# ArduinoInterface_v4_1.net
KiCad netlist of a schematic drawn in EAGLE
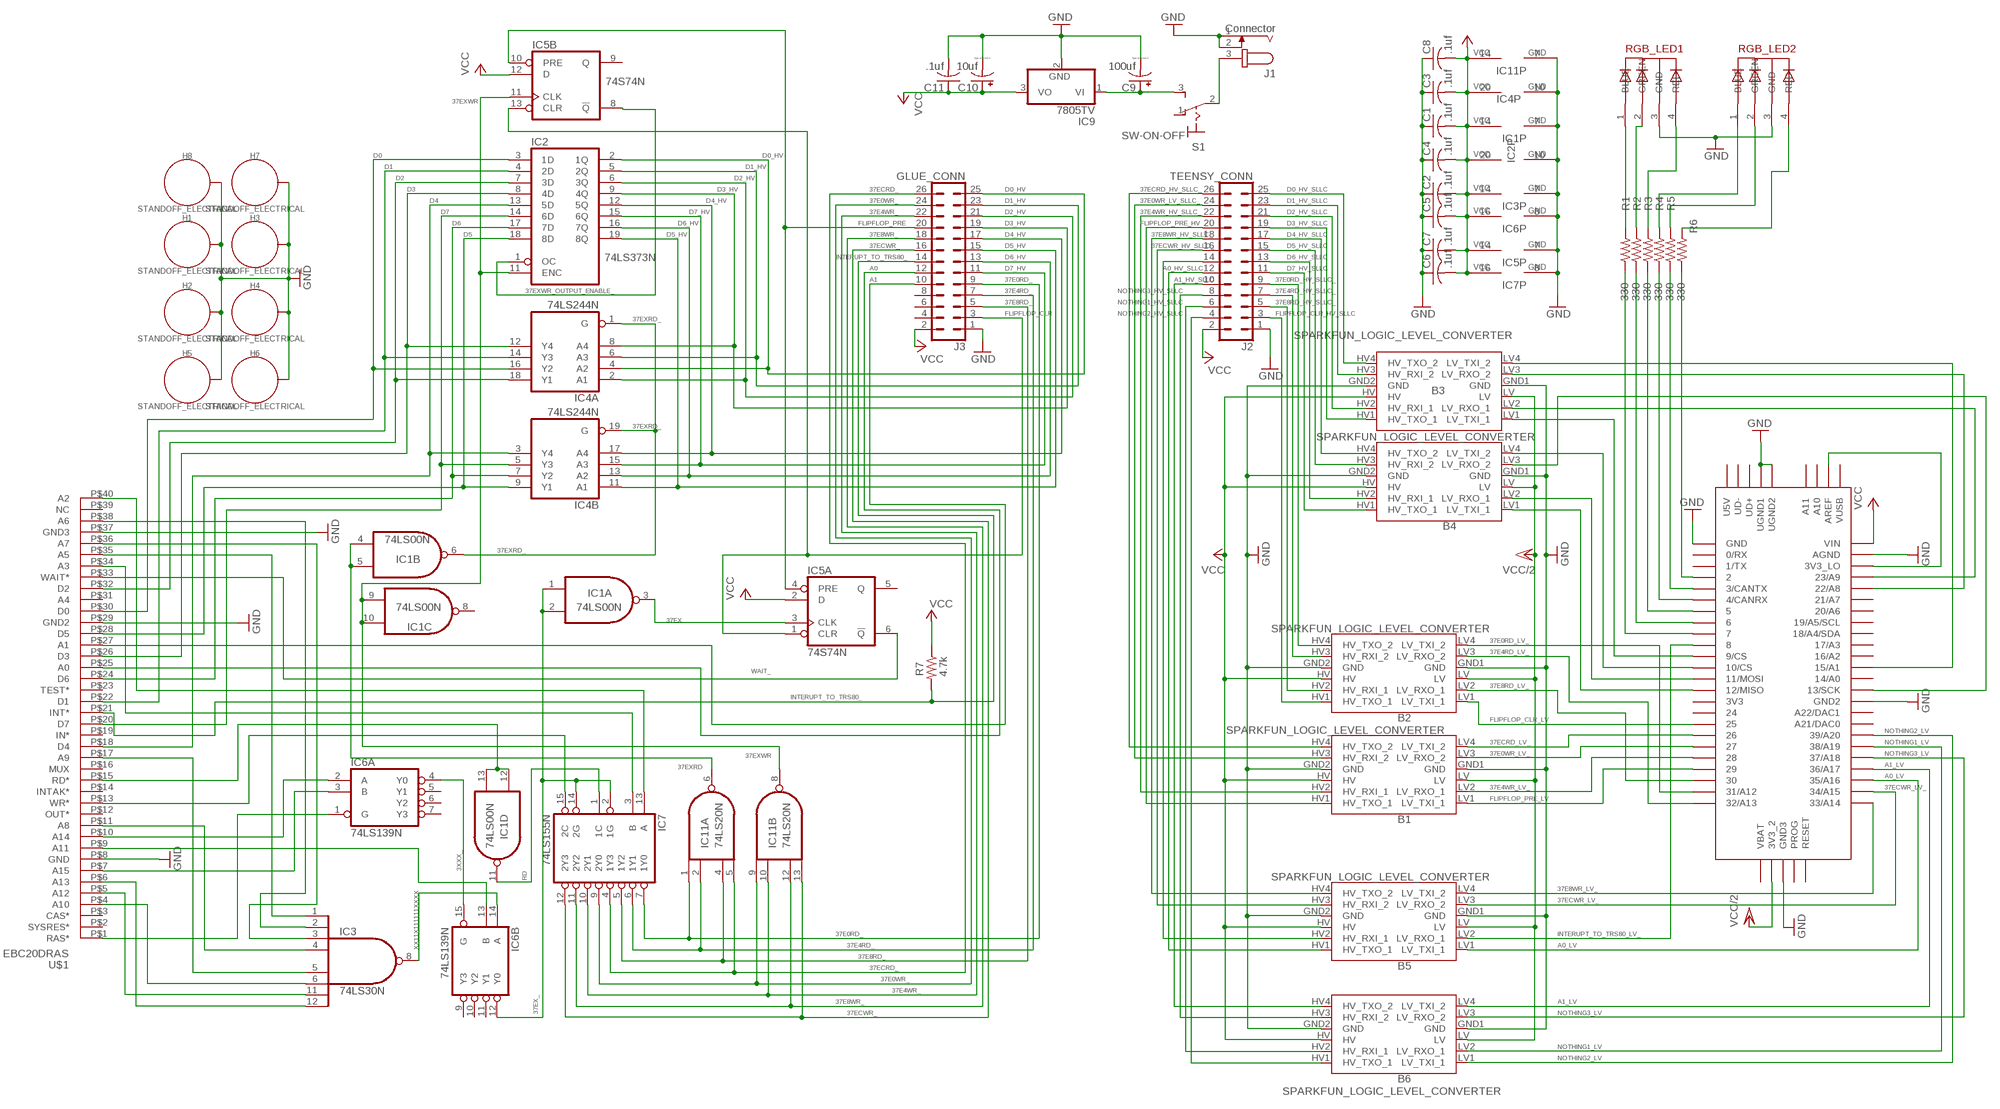
[diagram p0: schematic, sheet 1]

(export (version "E")
  (design (tool "Eeschema 10.0.6"))
  (components
    (comp (ref "B1")
      (value "SPARKFUN_LOGIC_LEVEL_CONVERTER")
      (footprint "eagle-import:SPARKFUN_LOGIC_LEVEL_CONVERTER")
      (libsource (lib "eagle-import") (part "SPARKFUN_LOGIC_LEVEL_CONVERTER"))
    )
    (comp (ref "B2")
      (value "SPARKFUN_LOGIC_LEVEL_CONVERTER")
      (footprint "eagle-import:SPARKFUN_LOGIC_LEVEL_CONVERTER")
      (libsource (lib "eagle-import") (part "SPARKFUN_LOGIC_LEVEL_CONVERTER"))
    )
    (comp (ref "B3")
      (value "SPARKFUN_LOGIC_LEVEL_CONVERTER")
      (footprint "eagle-import:SPARKFUN_LOGIC_LEVEL_CONVERTER")
      (libsource (lib "eagle-import") (part "SPARKFUN_LOGIC_LEVEL_CONVERTER"))
    )
    (comp (ref "B4")
      (value "SPARKFUN_LOGIC_LEVEL_CONVERTER")
      (footprint "eagle-import:SPARKFUN_LOGIC_LEVEL_CONVERTER")
      (libsource (lib "eagle-import") (part "SPARKFUN_LOGIC_LEVEL_CONVERTER"))
    )
    (comp (ref "B5")
      (value "SPARKFUN_LOGIC_LEVEL_CONVERTER")
      (footprint "eagle-import:SPARKFUN_LOGIC_LEVEL_CONVERTER")
      (libsource (lib "eagle-import") (part "SPARKFUN_LOGIC_LEVEL_CONVERTER"))
    )
    (comp (ref "B6")
      (value "SPARKFUN_LOGIC_LEVEL_CONVERTER")
      (footprint "eagle-import:SPARKFUN_LOGIC_LEVEL_CONVERTER")
      (libsource (lib "eagle-import") (part "SPARKFUN_LOGIC_LEVEL_CONVERTER"))
    )
    (comp (ref "C1")
      (value ".1uf")
      (footprint "eagle-import:C025-025X050")
      (libsource (lib "eagle-import") (part "C-US025-025X050"))
    )
    (comp (ref "C2")
      (value ".1uf")
      (footprint "eagle-import:C025-025X050")
      (libsource (lib "eagle-import") (part "C-US025-025X050"))
    )
    (comp (ref "C3")
      (value ".1uf")
      (footprint "eagle-import:C025-025X050")
      (libsource (lib "eagle-import") (part "C-US025-025X050"))
    )
    (comp (ref "C4")
      (value ".1uf")
      (footprint "eagle-import:C025-025X050")
      (libsource (lib "eagle-import") (part "C-US025-025X050"))
    )
    (comp (ref "C5")
      (value ".1uf")
      (footprint "eagle-import:C025-025X050")
      (libsource (lib "eagle-import") (part "C-US025-025X050"))
    )
    (comp (ref "C6")
      (value ".1uf")
      (footprint "eagle-import:C025-025X050")
      (libsource (lib "eagle-import") (part "C-US025-025X050"))
    )
    (comp (ref "C7")
      (value ".1uf")
      (footprint "eagle-import:C025-025X050")
      (libsource (lib "eagle-import") (part "C-US025-025X050"))
    )
    (comp (ref "C8")
      (value ".1uf")
      (footprint "eagle-import:C025-025X050")
      (libsource (lib "eagle-import") (part "C-US025-025X050"))
    )
    (comp (ref "C9")
      (value "100uf")
      (footprint "eagle-import:E5-6")
      (libsource (lib "eagle-import") (part "CPOL-USE5-6"))
    )
    (comp (ref "C10")
      (value "10uf")
      (footprint "eagle-import:E5-6")
      (libsource (lib "eagle-import") (part "CPOL-USE5-6"))
    )
    (comp (ref "C11")
      (value ".1uf")
      (footprint "eagle-import:C025-025X050")
      (libsource (lib "eagle-import") (part "C-US025-025X050"))
    )
    (comp (ref "H1")
      (value "STANDOFF_ELECTRICAL")
      (footprint "eagle-import:STANDOFF-ELECTRICAL")
      (libsource (lib "eagle-import") (part "STANDOFF_ELECTRICAL"))
    )
    (comp (ref "H2")
      (value "STANDOFF_ELECTRICAL")
      (footprint "eagle-import:STANDOFF-ELECTRICAL")
      (libsource (lib "eagle-import") (part "STANDOFF_ELECTRICAL"))
    )
    (comp (ref "H3")
      (value "STANDOFF_ELECTRICAL")
      (footprint "eagle-import:STANDOFF-ELECTRICAL")
      (libsource (lib "eagle-import") (part "STANDOFF_ELECTRICAL"))
    )
    (comp (ref "H4")
      (value "STANDOFF_ELECTRICAL")
      (footprint "eagle-import:STANDOFF-ELECTRICAL")
      (libsource (lib "eagle-import") (part "STANDOFF_ELECTRICAL"))
    )
    (comp (ref "H5")
      (value "STANDOFF_ELECTRICAL")
      (footprint "eagle-import:STANDOFF-ELECTRICAL")
      (libsource (lib "eagle-import") (part "STANDOFF_ELECTRICAL"))
    )
    (comp (ref "H6")
      (value "STANDOFF_ELECTRICAL")
      (footprint "eagle-import:STANDOFF-ELECTRICAL")
      (libsource (lib "eagle-import") (part "STANDOFF_ELECTRICAL"))
    )
    (comp (ref "H7")
      (value "STANDOFF_ELECTRICAL")
      (footprint "eagle-import:STANDOFF-ELECTRICAL")
      (libsource (lib "eagle-import") (part "STANDOFF_ELECTRICAL"))
    )
    (comp (ref "H8")
      (value "STANDOFF_ELECTRICAL")
      (footprint "eagle-import:STANDOFF-ELECTRICAL")
      (libsource (lib "eagle-import") (part "STANDOFF_ELECTRICAL"))
    )
    (comp (ref "IC1")
      (value "74LS00N")
      (footprint "eagle-import:DIL14")
      (libsource (lib "eagle-import") (part "7400NLS"))
    )
    (comp (ref "IC2")
      (value "74LS373N")
      (footprint "eagle-import:DIL20")
      (libsource (lib "eagle-import") (part "74373NLS"))
    )
    (comp (ref "IC3")
      (value "74LS30N")
      (footprint "eagle-import:DIL14")
      (libsource (lib "eagle-import") (part "7430NLS"))
    )
    (comp (ref "IC4")
      (value "74LS244N")
      (footprint "eagle-import:DIL20")
      (libsource (lib "eagle-import") (part "74244NLS"))
    )
    (comp (ref "IC5")
      (value "74S74N")
      (footprint "eagle-import:DIL14")
      (libsource (lib "eagle-import") (part "7474NS"))
    )
    (comp (ref "IC6")
      (value "74LS139N")
      (footprint "eagle-import:DIL16")
      (libsource (lib "eagle-import") (part "74139NLS"))
    )
    (comp (ref "IC7")
      (value "74LS155N")
      (footprint "eagle-import:DIL16")
      (libsource (lib "eagle-import") (part "74155NLS"))
    )
    (comp (ref "IC9")
      (value "7805TV")
      (footprint "eagle-import:TO220V")
      (libsource (lib "eagle-import") (part "78TV05"))
    )
    (comp (ref "IC11")
      (value "74LS20N")
      (footprint "eagle-import:DIL14")
      (libsource (lib "eagle-import") (part "7420NLS"))
    )
    (comp (ref "J1")
      (value "Connector")
      (footprint "eagle-import:SPC4077")
      (libsource (lib "eagle-import") (part "JACK-PLUG0"))
    )
    (comp (ref "J2")
      (value "TEENSY_CONN")
      (footprint "eagle-import:2X13")
      (libsource (lib "eagle-import") (part "CONN_13X22X13"))
    )
    (comp (ref "J3")
      (value "GLUE_CONN")
      (footprint "eagle-import:2X13")
      (libsource (lib "eagle-import") (part "CONN_13X22X13"))
    )
    (comp (ref "R1")
      (value "330")
      (footprint "eagle-import:0204V")
      (libsource (lib "eagle-import") (part "R-US_0204/2V"))
    )
    (comp (ref "R2")
      (value "330")
      (footprint "eagle-import:0204V")
      (libsource (lib "eagle-import") (part "R-US_0204/2V"))
    )
    (comp (ref "R3")
      (value "330")
      (footprint "eagle-import:0204V")
      (libsource (lib "eagle-import") (part "R-US_0204/2V"))
    )
    (comp (ref "R4")
      (value "330")
      (footprint "eagle-import:0204V")
      (libsource (lib "eagle-import") (part "R-US_0204/2V"))
    )
    (comp (ref "R5")
      (value "330")
      (footprint "eagle-import:0204V")
      (libsource (lib "eagle-import") (part "R-US_0204/2V"))
    )
    (comp (ref "R6")
      (value "330")
      (footprint "eagle-import:0204V")
      (libsource (lib "eagle-import") (part "R-US_0204/2V"))
    )
    (comp (ref "R7")
      (value "4.7k")
      (footprint "eagle-import:0204V")
      (libsource (lib "eagle-import") (part "R-US_0204/2V"))
    )
    (comp (ref "RGB_LED1")
      (value "5MMRGBLED")
      (footprint "eagle-import:LED5MMRGB")
      (libsource (lib "eagle-import") (part "5MMRGBLED"))
    )
    (comp (ref "RGB_LED2")
      (value "5MMRGBLED")
      (footprint "eagle-import:LED5MMRGB")
      (libsource (lib "eagle-import") (part "5MMRGBLED"))
    )
    (comp (ref "S1")
      (value "SW-ON-OFF")
      (footprint "eagle-import:M9040P")
      (libsource (lib "eagle-import") (part "M9040P"))
    )
    (comp (ref "U$1")
      (value "EBC20DRAS")
      (footprint "eagle-import:EBC20DRAS")
      (libsource (lib "eagle-import") (part "EBC20DRAS"))
    )
    (comp (ref "U$2")
      (value "TEENSY_3.5/3.6")
      (footprint "eagle-import:TEENSY_3.5_3.6")
      (libsource (lib "eagle-import") (part "TEENSY_3.5/3.6"))
    )
  )
  (nets
    (net (code "1") (name "/3XXX_") (class "Default")
      (node (ref "IC6") (pin "15") (pinfunction "G_15") (pintype "input"))
      (node (ref "IC6") (pin "4") (pinfunction "Y0_4") (pintype "output"))
    )
    (net (code "2") (name "/37E0RD_") (class "Default")
      (node (ref "IC11") (pin "1") (pinfunction "I0_1") (pintype "input"))
      (node (ref "IC7") (pin "7") (pinfunction "1Y0_7") (pintype "output"))
      (node (ref "J3") (pin "9") (pinfunction "9_9") (pintype "passive"))
    )
    (net (code "3") (name "/37E0RD_HV_SLLC_") (class "Default")
      (node (ref "B2") (pin "HV4") (pinfunction "HV_TXO_2_HV4") (pintype "bidirectional"))
      (node (ref "J2") (pin "9") (pinfunction "9_9") (pintype "passive"))
    )
    (net (code "4") (name "/37E0RD_LV_") (class "Default")
      (node (ref "B2") (pin "LV4") (pinfunction "LV_TXI_2_LV4") (pintype "bidirectional"))
      (node (ref "U$2") (pin "31/A12") (pinfunction "31/A12_31/A12") (pintype "bidirectional"))
    )
    (net (code "5") (name "/37E0WR_") (class "Default")
      (node (ref "IC11") (pin "9") (pinfunction "I0_9") (pintype "input"))
      (node (ref "IC7") (pin "9") (pinfunction "2Y0_9") (pintype "output"))
      (node (ref "J3") (pin "24") (pinfunction "24_24") (pintype "passive"))
    )
    (net (code "6") (name "/37E0WR_LV_") (class "Default")
      (node (ref "B1") (pin "LV3") (pinfunction "LV_RXO_2_LV3") (pintype "bidirectional"))
      (node (ref "U$2") (pin "27") (pinfunction "27_27") (pintype "bidirectional"))
    )
    (net (code "7") (name "/37E0WR_LV_SLLC_") (class "Default")
      (node (ref "B1") (pin "HV3") (pinfunction "HV_RXI_2_HV3") (pintype "bidirectional"))
      (node (ref "J2") (pin "24") (pinfunction "24_24") (pintype "passive"))
    )
    (net (code "8") (name "/37E4RD_") (class "Default")
      (node (ref "IC11") (pin "2") (pinfunction "I1_2") (pintype "input"))
      (node (ref "IC7") (pin "6") (pinfunction "1Y1_6") (pintype "output"))
      (node (ref "J3") (pin "7") (pinfunction "7_7") (pintype "passive"))
    )
    (net (code "9") (name "/37E4RD_HV_SLLC_") (class "Default")
      (node (ref "B2") (pin "HV3") (pinfunction "HV_RXI_2_HV3") (pintype "bidirectional"))
      (node (ref "J2") (pin "7") (pinfunction "7_7") (pintype "passive"))
    )
    (net (code "10") (name "/37E4RD_LV_") (class "Default")
      (node (ref "B2") (pin "LV3") (pinfunction "LV_RXO_2_LV3") (pintype "bidirectional"))
      (node (ref "U$2") (pin "32/A13") (pinfunction "32/A13_32/A13") (pintype "bidirectional"))
    )
    (net (code "11") (name "/37E4WR_") (class "Default")
      (node (ref "IC11") (pin "10") (pinfunction "I1_10") (pintype "input"))
      (node (ref "IC7") (pin "10") (pinfunction "2Y1_10") (pintype "output"))
      (node (ref "J3") (pin "22") (pinfunction "22_22") (pintype "passive"))
    )
    (net (code "12") (name "/37E4WR_HV_SLLC_") (class "Default")
      (node (ref "B1") (pin "HV2") (pinfunction "HV_RXI_1_HV2") (pintype "bidirectional"))
      (node (ref "J2") (pin "22") (pinfunction "22_22") (pintype "passive"))
    )
    (net (code "13") (name "/37E4WR_LV_") (class "Default")
      (node (ref "B1") (pin "LV2") (pinfunction "LV_RXO_1_LV2") (pintype "bidirectional"))
      (node (ref "U$2") (pin "28") (pinfunction "28_28") (pintype "bidirectional"))
    )
    (net (code "14") (name "/37E8RD_") (class "Default")
      (node (ref "IC11") (pin "4") (pinfunction "I2_4") (pintype "input"))
      (node (ref "IC7") (pin "5") (pinfunction "1Y2_5") (pintype "output"))
      (node (ref "J3") (pin "5") (pinfunction "5_5") (pintype "passive"))
    )
    (net (code "15") (name "/37E8RD_HV_SLLC_") (class "Default")
      (node (ref "B2") (pin "HV2") (pinfunction "HV_RXI_1_HV2") (pintype "bidirectional"))
      (node (ref "J2") (pin "5") (pinfunction "5_5") (pintype "passive"))
    )
    (net (code "16") (name "/37E8RD_LV_") (class "Default")
      (node (ref "B2") (pin "LV2") (pinfunction "LV_RXO_1_LV2") (pintype "bidirectional"))
      (node (ref "U$2") (pin "30") (pinfunction "30_30") (pintype "bidirectional"))
    )
    (net (code "17") (name "/37E8WR_") (class "Default")
      (node (ref "IC11") (pin "12") (pinfunction "I2_12") (pintype "input"))
      (node (ref "IC7") (pin "11") (pinfunction "2Y2_11") (pintype "output"))
      (node (ref "J3") (pin "18") (pinfunction "18_18") (pintype "passive"))
    )
    (net (code "18") (name "/37E8WR_HV_SLLC_") (class "Default")
      (node (ref "B5") (pin "HV4") (pinfunction "HV_TXO_2_HV4") (pintype "bidirectional"))
      (node (ref "J2") (pin "18") (pinfunction "18_18") (pintype "passive"))
    )
    (net (code "19") (name "/37E8WR_LV_") (class "Default")
      (node (ref "B5") (pin "LV4") (pinfunction "LV_TXI_2_LV4") (pintype "bidirectional"))
      (node (ref "U$2") (pin "33/A14") (pinfunction "33/A14_33/A14") (pintype "bidirectional"))
    )
    (net (code "20") (name "/37ECRD_") (class "Default")
      (node (ref "IC11") (pin "5") (pinfunction "I3_5") (pintype "input"))
      (node (ref "IC7") (pin "4") (pinfunction "1Y3_4") (pintype "output"))
      (node (ref "J3") (pin "26") (pinfunction "26_26") (pintype "passive"))
    )
    (net (code "21") (name "/37ECRD_HV_SLLC_") (class "Default")
      (node (ref "B1") (pin "HV4") (pinfunction "HV_TXO_2_HV4") (pintype "bidirectional"))
      (node (ref "J2") (pin "26") (pinfunction "26_26") (pintype "passive"))
    )
    (net (code "22") (name "/37ECRD_LV_") (class "Default")
      (node (ref "B1") (pin "LV4") (pinfunction "LV_TXI_2_LV4") (pintype "bidirectional"))
      (node (ref "U$2") (pin "26") (pinfunction "26_26") (pintype "bidirectional"))
    )
    (net (code "23") (name "/37ECWR_") (class "Default")
      (node (ref "IC11") (pin "13") (pinfunction "I3_13") (pintype "input"))
      (node (ref "IC7") (pin "12") (pinfunction "2Y3_12") (pintype "output"))
      (node (ref "J3") (pin "16") (pinfunction "16_16") (pintype "passive"))
    )
    (net (code "24") (name "/37ECWR_HV_SLLC_") (class "Default")
      (node (ref "B5") (pin "HV3") (pinfunction "HV_RXI_2_HV3") (pintype "bidirectional"))
      (node (ref "J2") (pin "16") (pinfunction "16_16") (pintype "passive"))
    )
    (net (code "25") (name "/37ECWR_LV_") (class "Default")
      (node (ref "B5") (pin "LV3") (pinfunction "LV_RXO_2_LV3") (pintype "bidirectional"))
      (node (ref "U$2") (pin "34/A15") (pinfunction "34/A15_34/A15") (pintype "bidirectional"))
    )
    (net (code "26") (name "/37EX") (class "Default")
      (node (ref "IC1") (pin "3") (pinfunction "O_3") (pintype "output"))
      (node (ref "IC5") (pin "3") (pinfunction "CLK_3") (pintype "input"))
    )
    (net (code "27") (name "/37EXRD") (class "Default")
      (node (ref "IC1") (pin "4") (pinfunction "I0_4") (pintype "input"))
      (node (ref "IC1") (pin "5") (pinfunction "I1_5") (pintype "input"))
      (node (ref "IC11") (pin "6") (pinfunction "O_6") (pintype "output"))
    )
    (net (code "28") (name "/37EXRD_") (class "Default")
      (node (ref "IC1") (pin "6") (pinfunction "O_6") (pintype "output"))
      (node (ref "IC4") (pin "1") (pinfunction "G_1") (pintype "input"))
      (node (ref "IC4") (pin "19") (pinfunction "G_19") (pintype "input"))
    )
    (net (code "29") (name "/37EXWR") (class "Default")
      (node (ref "IC1") (pin "10") (pinfunction "I1_10") (pintype "input"))
      (node (ref "IC1") (pin "9") (pinfunction "I0_9") (pintype "input"))
      (node (ref "IC11") (pin "8") (pinfunction "O_8") (pintype "output"))
      (node (ref "IC2") (pin "11") (pinfunction "ENC_11") (pintype "input"))
      (node (ref "IC5") (pin "11") (pinfunction "CLK_11") (pintype "input"))
    )
    (net (code "30") (name "/37EXWR_OUTPUT_ENABLE_") (class "Default")
      (node (ref "IC2") (pin "1") (pinfunction "OC_1") (pintype "input"))
      (node (ref "IC5") (pin "8") (pinfunction "~{Q}_8") (pintype "output"))
    )
    (net (code "31") (name "/37EX_") (class "Default")
      (node (ref "IC1") (pin "1") (pinfunction "I0_1") (pintype "input"))
      (node (ref "IC1") (pin "2") (pinfunction "I1_2") (pintype "input"))
      (node (ref "IC6") (pin "12") (pinfunction "Y0_12") (pintype "output"))
      (node (ref "IC7") (pin "14") (pinfunction "2G_14") (pintype "input"))
      (node (ref "IC7") (pin "2") (pinfunction "1G_2") (pintype "input"))
    )
    (net (code "32") (name "/A0") (class "Default")
      (node (ref "J3") (pin "12") (pinfunction "12_12") (pintype "passive"))
      (node (ref "U$1") (pin "P$25") (pinfunction "A0_P$25") (pintype "bidirectional"))
    )
    (net (code "33") (name "/A0_HV_SLLC") (class "Default")
      (node (ref "B5") (pin "HV1") (pinfunction "HV_TXO_1_HV1") (pintype "bidirectional"))
      (node (ref "J2") (pin "12") (pinfunction "12_12") (pintype "passive"))
    )
    (net (code "34") (name "/A0_LV") (class "Default")
      (node (ref "B5") (pin "LV1") (pinfunction "LV_TXI_1_LV1") (pintype "bidirectional"))
      (node (ref "U$2") (pin "35/A16") (pinfunction "35/A16_35/A16") (pintype "bidirectional"))
    )
    (net (code "35") (name "/A1") (class "Default")
      (node (ref "J3") (pin "10") (pinfunction "10_10") (pintype "passive"))
      (node (ref "U$1") (pin "P$27") (pinfunction "A1_P$27") (pintype "bidirectional"))
    )
    (net (code "36") (name "/A1_HV_SLLC") (class "Default")
      (node (ref "B6") (pin "HV4") (pinfunction "HV_TXO_2_HV4") (pintype "bidirectional"))
      (node (ref "J2") (pin "10") (pinfunction "10_10") (pintype "passive"))
    )
    (net (code "37") (name "/A1_LV") (class "Default")
      (node (ref "B6") (pin "LV4") (pinfunction "LV_TXI_2_LV4") (pintype "bidirectional"))
      (node (ref "U$2") (pin "36/A17") (pinfunction "36/A17_36/A17") (pintype "bidirectional"))
    )
    (net (code "38") (name "/D0") (class "Default")
      (node (ref "IC2") (pin "3") (pinfunction "1D_3") (pintype "input"))
      (node (ref "IC4") (pin "16") (pinfunction "Y2_16") (pintype "tri_state"))
      (node (ref "U$1") (pin "P$30") (pinfunction "D0_P$30") (pintype "bidirectional"))
    )
    (net (code "39") (name "/D0_HV") (class "Default")
      (node (ref "IC2") (pin "2") (pinfunction "1Q_2") (pintype "tri_state"))
      (node (ref "IC4") (pin "4") (pinfunction "A2_4") (pintype "input"))
      (node (ref "J3") (pin "25") (pinfunction "25_25") (pintype "passive"))
    )
    (net (code "40") (name "/D0_HV_SLLC") (class "Default")
      (node (ref "B3") (pin "HV4") (pinfunction "HV_TXO_2_HV4") (pintype "bidirectional"))
      (node (ref "J2") (pin "25") (pinfunction "25_25") (pintype "passive"))
    )
    (net (code "41") (name "/D1") (class "Default")
      (node (ref "IC2") (pin "4") (pinfunction "2D_4") (pintype "input"))
      (node (ref "IC4") (pin "14") (pinfunction "Y3_14") (pintype "tri_state"))
      (node (ref "U$1") (pin "P$22") (pinfunction "D1_P$22") (pintype "bidirectional"))
    )
    (net (code "42") (name "/D1_HV") (class "Default")
      (node (ref "IC2") (pin "5") (pinfunction "2Q_5") (pintype "tri_state"))
      (node (ref "IC4") (pin "6") (pinfunction "A3_6") (pintype "input"))
      (node (ref "J3") (pin "23") (pinfunction "23_23") (pintype "passive"))
    )
    (net (code "43") (name "/D1_HV_SLLC") (class "Default")
      (node (ref "B3") (pin "HV3") (pinfunction "HV_RXI_2_HV3") (pintype "bidirectional"))
      (node (ref "J2") (pin "23") (pinfunction "23_23") (pintype "passive"))
    )
    (net (code "44") (name "/D2") (class "Default")
      (node (ref "IC2") (pin "7") (pinfunction "3D_7") (pintype "input"))
      (node (ref "IC4") (pin "18") (pinfunction "Y1_18") (pintype "tri_state"))
      (node (ref "U$1") (pin "P$32") (pinfunction "D2_P$32") (pintype "bidirectional"))
    )
    (net (code "45") (name "/D2_HV") (class "Default")
      (node (ref "IC2") (pin "6") (pinfunction "3Q_6") (pintype "tri_state"))
      (node (ref "IC4") (pin "2") (pinfunction "A1_2") (pintype "input"))
      (node (ref "J3") (pin "21") (pinfunction "21_21") (pintype "passive"))
    )
    (net (code "46") (name "/D2_HV_SLLC") (class "Default")
      (node (ref "B3") (pin "HV2") (pinfunction "HV_RXI_1_HV2") (pintype "bidirectional"))
      (node (ref "J2") (pin "21") (pinfunction "21_21") (pintype "passive"))
    )
    (net (code "47") (name "/D3") (class "Default")
      (node (ref "IC2") (pin "8") (pinfunction "4D_8") (pintype "input"))
      (node (ref "IC4") (pin "12") (pinfunction "Y4_12") (pintype "tri_state"))
      (node (ref "U$1") (pin "P$26") (pinfunction "D3_P$26") (pintype "bidirectional"))
    )
    (net (code "48") (name "/D3_HV") (class "Default")
      (node (ref "IC2") (pin "9") (pinfunction "4Q_9") (pintype "tri_state"))
      (node (ref "IC4") (pin "8") (pinfunction "A4_8") (pintype "input"))
      (node (ref "J3") (pin "19") (pinfunction "19_19") (pintype "passive"))
    )
    (net (code "49") (name "/D3_HV_SLLC") (class "Default")
      (node (ref "B3") (pin "HV1") (pinfunction "HV_TXO_1_HV1") (pintype "bidirectional"))
      (node (ref "J2") (pin "19") (pinfunction "19_19") (pintype "passive"))
    )
    (net (code "50") (name "/D4") (class "Default")
      (node (ref "IC2") (pin "13") (pinfunction "5D_13") (pintype "input"))
      (node (ref "IC4") (pin "3") (pinfunction "Y4_3") (pintype "tri_state"))
      (node (ref "U$1") (pin "P$18") (pinfunction "D4_P$18") (pintype "bidirectional"))
    )
    (net (code "51") (name "/D4_HV") (class "Default")
      (node (ref "IC2") (pin "12") (pinfunction "5Q_12") (pintype "tri_state"))
      (node (ref "IC4") (pin "17") (pinfunction "A4_17") (pintype "input"))
      (node (ref "J3") (pin "17") (pinfunction "17_17") (pintype "passive"))
    )
    (net (code "52") (name "/D4_HV_SLLC") (class "Default")
      (node (ref "B4") (pin "HV4") (pinfunction "HV_TXO_2_HV4") (pintype "bidirectional"))
      (node (ref "J2") (pin "17") (pinfunction "17_17") (pintype "passive"))
    )
    (net (code "53") (name "/D5") (class "Default")
      (node (ref "IC2") (pin "18") (pinfunction "8D_18") (pintype "input"))
      (node (ref "IC4") (pin "9") (pinfunction "Y1_9") (pintype "tri_state"))
      (node (ref "U$1") (pin "P$28") (pinfunction "D5_P$28") (pintype "bidirectional"))
    )
    (net (code "54") (name "/D5_HV") (class "Default")
      (node (ref "IC2") (pin "19") (pinfunction "8Q_19") (pintype "tri_state"))
      (node (ref "IC4") (pin "11") (pinfunction "A1_11") (pintype "input"))
      (node (ref "J3") (pin "15") (pinfunction "15_15") (pintype "passive"))
    )
    (net (code "55") (name "/D5_HV_SLLC") (class "Default")
      (node (ref "B4") (pin "HV3") (pinfunction "HV_RXI_2_HV3") (pintype "bidirectional"))
      (node (ref "J2") (pin "15") (pinfunction "15_15") (pintype "passive"))
    )
    (net (code "56") (name "/D6") (class "Default")
      (node (ref "IC2") (pin "17") (pinfunction "7D_17") (pintype "input"))
      (node (ref "IC4") (pin "7") (pinfunction "Y2_7") (pintype "tri_state"))
      (node (ref "U$1") (pin "P$24") (pinfunction "D6_P$24") (pintype "bidirectional"))
    )
    (net (code "57") (name "/D6_HV") (class "Default")
      (node (ref "IC2") (pin "16") (pinfunction "7Q_16") (pintype "tri_state"))
      (node (ref "IC4") (pin "13") (pinfunction "A2_13") (pintype "input"))
      (node (ref "J3") (pin "13") (pinfunction "13_13") (pintype "passive"))
    )
    (net (code "58") (name "/D6_HV_SLLC") (class "Default")
      (node (ref "B4") (pin "HV2") (pinfunction "HV_RXI_1_HV2") (pintype "bidirectional"))
      (node (ref "J2") (pin "13") (pinfunction "13_13") (pintype "passive"))
    )
    (net (code "59") (name "/D7") (class "Default")
      (node (ref "IC2") (pin "14") (pinfunction "6D_14") (pintype "input"))
      (node (ref "IC4") (pin "5") (pinfunction "Y3_5") (pintype "tri_state"))
      (node (ref "U$1") (pin "P$20") (pinfunction "D7_P$20") (pintype "bidirectional"))
    )
    (net (code "60") (name "/D7_HV") (class "Default")
      (node (ref "IC2") (pin "15") (pinfunction "6Q_15") (pintype "tri_state"))
      (node (ref "IC4") (pin "15") (pinfunction "A3_15") (pintype "input"))
      (node (ref "J3") (pin "11") (pinfunction "11_11") (pintype "passive"))
    )
    (net (code "61") (name "/D7_HV_SLLC") (class "Default")
      (node (ref "B4") (pin "HV1") (pinfunction "HV_TXO_1_HV1") (pintype "bidirectional"))
      (node (ref "J2") (pin "11") (pinfunction "11_11") (pintype "passive"))
    )
    (net (code "62") (name "/FLIPFLOP_CLR") (class "Default")
      (node (ref "IC5") (pin "1") (pinfunction "CLR_1") (pintype "input"))
      (node (ref "IC5") (pin "13") (pinfunction "CLR_13") (pintype "input"))
      (node (ref "J3") (pin "3") (pinfunction "3_3") (pintype "passive"))
    )
    (net (code "63") (name "/FLIPFLOP_CLR_HV_SLLC") (class "Default")
      (node (ref "B2") (pin "HV1") (pinfunction "HV_TXO_1_HV1") (pintype "bidirectional"))
      (node (ref "J2") (pin "3") (pinfunction "3_3") (pintype "passive"))
    )
    (net (code "64") (name "/FLIPFLOP_CLR_LV") (class "Default")
      (node (ref "B2") (pin "LV1") (pinfunction "LV_TXI_1_LV1") (pintype "bidirectional"))
      (node (ref "U$2") (pin "25") (pinfunction "25_25") (pintype "bidirectional"))
    )
    (net (code "65") (name "/FLIPFLOP_PRE") (class "Default")
      (node (ref "IC5") (pin "10") (pinfunction "PRE_10") (pintype "input"))
      (node (ref "IC5") (pin "4") (pinfunction "PRE_4") (pintype "input"))
      (node (ref "J3") (pin "20") (pinfunction "20_20") (pintype "passive"))
    )
    (net (code "66") (name "/FLIPFLOP_PRE_HV") (class "Default")
      (node (ref "B1") (pin "HV1") (pinfunction "HV_TXO_1_HV1") (pintype "bidirectional"))
      (node (ref "J2") (pin "20") (pinfunction "20_20") (pintype "passive"))
    )
    (net (code "67") (name "/FLIPFLOP_PRE_LV") (class "Default")
      (node (ref "B1") (pin "LV1") (pinfunction "LV_TXI_1_LV1") (pintype "bidirectional"))
      (node (ref "U$2") (pin "29") (pinfunction "29_29") (pintype "bidirectional"))
    )
    (net (code "68") (name "/INTERUPT_TO_TRS80_") (class "Default")
      (node (ref "J3") (pin "14") (pinfunction "14_14") (pintype "passive"))
      (node (ref "R7") (pin "2") (pinfunction "2_2") (pintype "passive"))
      (node (ref "U$1") (pin "P$21") (pinfunction "INT*_P$21") (pintype "bidirectional"))
    )
    (net (code "69") (name "/INTERUPT_TO_TRS80_LV_") (class "Default")
      (node (ref "B5") (pin "LV2") (pinfunction "LV_RXO_1_LV2") (pintype "bidirectional"))
      (node (ref "U$2") (pin "8") (pinfunction "8_8") (pintype "bidirectional"))
    )
    (net (code "70") (name "/NOTHING1_HV_SLLC") (class "Default")
      (node (ref "B6") (pin "HV2") (pinfunction "HV_RXI_1_HV2") (pintype "bidirectional"))
      (node (ref "J2") (pin "6") (pinfunction "6_6") (pintype "passive"))
    )
    (net (code "71") (name "/NOTHING1_LV") (class "Default")
      (node (ref "B6") (pin "LV2") (pinfunction "LV_RXO_1_LV2") (pintype "bidirectional"))
      (node (ref "U$2") (pin "38/A19") (pinfunction "38/A19_38/A19") (pintype "bidirectional"))
    )
    (net (code "72") (name "/NOTHING2_HV_SLLC") (class "Default")
      (node (ref "B6") (pin "HV1") (pinfunction "HV_TXO_1_HV1") (pintype "bidirectional"))
      (node (ref "J2") (pin "4") (pinfunction "4_4") (pintype "passive"))
    )
    (net (code "73") (name "/NOTHING2_LV") (class "Default")
      (node (ref "B6") (pin "LV1") (pinfunction "LV_TXI_1_LV1") (pintype "bidirectional"))
      (node (ref "U$2") (pin "39/A20") (pinfunction "39/A20_39/A20") (pintype "bidirectional"))
    )
    (net (code "74") (name "/NOTHING3_HV_SLLC") (class "Default")
      (node (ref "B6") (pin "HV3") (pinfunction "HV_RXI_2_HV3") (pintype "bidirectional"))
      (node (ref "J2") (pin "8") (pinfunction "8_8") (pintype "passive"))
    )
    (net (code "75") (name "/NOTHING3_LV") (class "Default")
      (node (ref "B6") (pin "LV3") (pinfunction "LV_RXO_2_LV3") (pintype "bidirectional"))
      (node (ref "U$2") (pin "37/A18") (pinfunction "37/A18_37/A18") (pintype "bidirectional"))
    )
    (net (code "76") (name "/RD") (class "Default")
      (node (ref "IC1") (pin "11") (pinfunction "O_11") (pintype "output"))
      (node (ref "IC7") (pin "1") (pinfunction "1C_1") (pintype "input"))
    )
    (net (code "77") (name "/WAIT_") (class "Default")
      (node (ref "IC5") (pin "6") (pinfunction "~{Q}_6") (pintype "output"))
      (node (ref "U$1") (pin "P$33") (pinfunction "WAIT*_P$33") (pintype "bidirectional"))
    )
    (net (code "78") (name "/XX11X111111XXXX") (class "Default")
      (node (ref "IC3") (pin "8") (pinfunction "O_8") (pintype "output"))
      (node (ref "IC6") (pin "14") (pinfunction "A_14") (pintype "input"))
    )
    (net (code "79") (name "GND") (class "Default")
      (node (ref "B1") (pin "GND1") (pinfunction "GND_GND1") (pintype "power_in"))
      (node (ref "B1") (pin "GND2") (pinfunction "GND_GND2") (pintype "power_in"))
      (node (ref "B2") (pin "GND1") (pinfunction "GND_GND1") (pintype "power_in"))
      (node (ref "B2") (pin "GND2") (pinfunction "GND_GND2") (pintype "power_in"))
      (node (ref "B3") (pin "GND1") (pinfunction "GND_GND1") (pintype "power_in"))
      (node (ref "B3") (pin "GND2") (pinfunction "GND_GND2") (pintype "power_in"))
      (node (ref "B4") (pin "GND1") (pinfunction "GND_GND1") (pintype "power_in"))
      (node (ref "B4") (pin "GND2") (pinfunction "GND_GND2") (pintype "power_in"))
      (node (ref "B5") (pin "GND1") (pinfunction "GND_GND1") (pintype "power_in"))
      (node (ref "B5") (pin "GND2") (pinfunction "GND_GND2") (pintype "power_in"))
      (node (ref "B6") (pin "GND1") (pinfunction "GND_GND1") (pintype "power_in"))
      (node (ref "B6") (pin "GND2") (pinfunction "GND_GND2") (pintype "power_in"))
      (node (ref "C1") (pin "1") (pinfunction "1_1") (pintype "passive"))
      (node (ref "C10") (pin "-") (pinfunction "-_-") (pintype "passive"))
      (node (ref "C11") (pin "2") (pinfunction "2_2") (pintype "passive"))
      (node (ref "C2") (pin "1") (pinfunction "1_1") (pintype "passive"))
      (node (ref "C3") (pin "1") (pinfunction "1_1") (pintype "passive"))
      (node (ref "C4") (pin "1") (pinfunction "1_1") (pintype "passive"))
      (node (ref "C5") (pin "1") (pinfunction "1_1") (pintype "passive"))
      (node (ref "C6") (pin "1") (pinfunction "1_1") (pintype "passive"))
      (node (ref "C7") (pin "1") (pinfunction "1_1") (pintype "passive"))
      (node (ref "C8") (pin "1") (pinfunction "1_1") (pintype "passive"))
      (node (ref "C9") (pin "-") (pinfunction "-_-") (pintype "passive"))
      (node (ref "H1") (pin "P1") (pinfunction "P$1_P1") (pintype "bidirectional"))
      (node (ref "H2") (pin "P1") (pinfunction "P$1_P1") (pintype "bidirectional"))
      (node (ref "H3") (pin "P1") (pinfunction "P$1_P1") (pintype "bidirectional"))
      (node (ref "H4") (pin "P1") (pinfunction "P$1_P1") (pintype "bidirectional"))
      (node (ref "H5") (pin "P1") (pinfunction "P$1_P1") (pintype "bidirectional"))
      (node (ref "H6") (pin "P1") (pinfunction "P$1_P1") (pintype "bidirectional"))
      (node (ref "H7") (pin "P1") (pinfunction "P$1_P1") (pintype "bidirectional"))
      (node (ref "H8") (pin "P1") (pinfunction "P$1_P1") (pintype "bidirectional"))
      (node (ref "IC1") (pin "7") (pinfunction "GND_7") (pintype "power_in"))
      (node (ref "IC11") (pin "7") (pinfunction "GND_7") (pintype "power_in"))
      (node (ref "IC2") (pin "10") (pinfunction "GND_10") (pintype "power_in"))
      (node (ref "IC3") (pin "7") (pinfunction "GND_7") (pintype "power_in"))
      (node (ref "IC4") (pin "10") (pinfunction "GND_10") (pintype "power_in"))
      (node (ref "IC5") (pin "7") (pinfunction "GND_7") (pintype "power_in"))
      (node (ref "IC6") (pin "8") (pinfunction "GND_8") (pintype "power_in"))
      (node (ref "IC7") (pin "8") (pinfunction "GND_8") (pintype "power_in"))
      (node (ref "IC9") (pin "2") (pinfunction "GND_2") (pintype "passive"))
      (node (ref "J1") (pin "1") (pinfunction "1_1") (pintype "passive"))
      (node (ref "J1") (pin "2") (pinfunction "2_2") (pintype "passive"))
      (node (ref "J2") (pin "1") (pinfunction "1_1") (pintype "passive"))
      (node (ref "J3") (pin "1") (pinfunction "1_1") (pintype "passive"))
      (node (ref "RGB_LED1") (pin "3") (pinfunction "GND_3") (pintype "bidirectional"))
      (node (ref "RGB_LED2") (pin "3") (pinfunction "GND_3") (pintype "bidirectional"))
      (node (ref "U$1") (pin "P$29") (pinfunction "GND2_P$29") (pintype "bidirectional"))
      (node (ref "U$1") (pin "P$37") (pinfunction "GND3_P$37") (pintype "bidirectional"))
      (node (ref "U$1") (pin "P$8") (pinfunction "GND_P$8") (pintype "bidirectional"))
      (node (ref "U$2") (pin "AGND") (pinfunction "AGND_AGND") (pintype "bidirectional"))
      (node (ref "U$2") (pin "GND") (pinfunction "GND_GND") (pintype "bidirectional"))
      (node (ref "U$2") (pin "GND2") (pinfunction "GND2_GND2") (pintype "bidirectional"))
      (node (ref "U$2") (pin "GND3") (pinfunction "GND3_GND3") (pintype "bidirectional"))
      (node (ref "U$2") (pin "UGND1") (pinfunction "UGND1_UGND1") (pintype "bidirectional"))
      (node (ref "U$2") (pin "UGND2") (pinfunction "UGND2_UGND2") (pintype "bidirectional"))
    )
    (net (code "80") (name "Net-(B3-LV_RXO_1)") (class "Default")
      (node (ref "B3") (pin "LV2") (pinfunction "LV_RXO_1_LV2") (pintype "bidirectional"))
      (node (ref "U$2") (pin "23/A9") (pinfunction "23/A9_23/A9") (pintype "bidirectional"))
    )
    (net (code "81") (name "Net-(B3-LV_RXO_2)") (class "Default")
      (node (ref "B3") (pin "LV3") (pinfunction "LV_RXO_2_LV3") (pintype "bidirectional"))
      (node (ref "U$2") (pin "22/A8") (pinfunction "22/A8_22/A8") (pintype "bidirectional"))
    )
    (net (code "82") (name "Net-(B3-LV_TXI_1)") (class "Default")
      (node (ref "B3") (pin "LV1") (pinfunction "LV_TXI_1_LV1") (pintype "bidirectional"))
      (node (ref "U$2") (pin "9/CS") (pinfunction "9/CS_9/CS") (pintype "bidirectional"))
    )
    (net (code "83") (name "Net-(B3-LV_TXI_2)") (class "Default")
      (node (ref "B3") (pin "LV4") (pinfunction "LV_TXI_2_LV4") (pintype "bidirectional"))
      (node (ref "U$2") (pin "15/A1") (pinfunction "15/A1_15/A1") (pintype "bidirectional"))
    )
    (net (code "84") (name "Net-(B4-LV_RXO_1)") (class "Default")
      (node (ref "B4") (pin "LV2") (pinfunction "LV_RXO_1_LV2") (pintype "bidirectional"))
      (node (ref "U$2") (pin "11/MOSI") (pinfunction "11/MOSI_11/MOSI") (pintype "bidirectional"))
    )
    (net (code "85") (name "Net-(B4-LV_RXO_2)") (class "Default")
      (node (ref "B4") (pin "LV3") (pinfunction "LV_RXO_2_LV3") (pintype "bidirectional"))
      (node (ref "U$2") (pin "13/SCK") (pinfunction "13/SCK_13/SCK") (pintype "bidirectional"))
    )
    (net (code "86") (name "Net-(B4-LV_TXI_1)") (class "Default")
      (node (ref "B4") (pin "LV1") (pinfunction "LV_TXI_1_LV1") (pintype "bidirectional"))
      (node (ref "U$2") (pin "12/MISO") (pinfunction "12/MISO_12/MISO") (pintype "bidirectional"))
    )
    (net (code "87") (name "Net-(B4-LV_TXI_2)") (class "Default")
      (node (ref "B4") (pin "LV4") (pinfunction "LV_TXI_2_LV4") (pintype "bidirectional"))
      (node (ref "U$2") (pin "10/CS") (pinfunction "10/CS_10/CS") (pintype "bidirectional"))
    )
    (net (code "88") (name "Net-(B5-HV_RXI_1)") (class "Default")
      (node (ref "B5") (pin "HV2") (pinfunction "HV_RXI_1_HV2") (pintype "bidirectional"))
      (node (ref "J2") (pin "14") (pinfunction "14_14") (pintype "passive"))
    )
    (net (code "89") (name "Net-(IC1D-I0)") (class "Default")
      (node (ref "IC1") (pin "12") (pinfunction "I0_12") (pintype "input"))
      (node (ref "IC1") (pin "13") (pinfunction "I1_13") (pintype "input"))
      (node (ref "U$1") (pin "P$15") (pinfunction "RD*_P$15") (pintype "bidirectional"))
    )
    (net (code "90") (name "Net-(IC3A-I0)") (class "Default")
      (node (ref "IC3") (pin "1") (pinfunction "I0_1") (pintype "input"))
      (node (ref "U$1") (pin "P$35") (pinfunction "A5_P$35") (pintype "bidirectional"))
    )
    (net (code "91") (name "Net-(IC3A-I1)") (class "Default")
      (node (ref "IC3") (pin "2") (pinfunction "I1_2") (pintype "input"))
      (node (ref "U$1") (pin "P$38") (pinfunction "A6_P$38") (pintype "bidirectional"))
    )
    (net (code "92") (name "Net-(IC3A-I2)") (class "Default")
      (node (ref "IC3") (pin "3") (pinfunction "I2_3") (pintype "input"))
      (node (ref "U$1") (pin "P$36") (pinfunction "A7_P$36") (pintype "bidirectional"))
    )
    (net (code "93") (name "Net-(IC3A-I3)") (class "Default")
      (node (ref "IC3") (pin "4") (pinfunction "I3_4") (pintype "input"))
      (node (ref "U$1") (pin "P$11") (pinfunction "A8_P$11") (pintype "bidirectional"))
    )
    (net (code "94") (name "Net-(IC3A-I4)") (class "Default")
      (node (ref "IC3") (pin "5") (pinfunction "I4_5") (pintype "input"))
      (node (ref "U$1") (pin "P$17") (pinfunction "A9_P$17") (pintype "bidirectional"))
    )
    (net (code "95") (name "Net-(IC3A-I5)") (class "Default")
      (node (ref "IC3") (pin "6") (pinfunction "I5_6") (pintype "input"))
      (node (ref "U$1") (pin "P$4") (pinfunction "A10_P$4") (pintype "bidirectional"))
    )
    (net (code "96") (name "Net-(IC3A-I6)") (class "Default")
      (node (ref "IC3") (pin "11") (pinfunction "I6_11") (pintype "input"))
      (node (ref "U$1") (pin "P$5") (pinfunction "A12_P$5") (pintype "bidirectional"))
    )
    (net (code "97") (name "Net-(IC3A-I7)") (class "Default")
      (node (ref "IC3") (pin "12") (pinfunction "I7_12") (pintype "input"))
      (node (ref "U$1") (pin "P$6") (pinfunction "A13_P$6") (pintype "bidirectional"))
    )
    (net (code "98") (name "Net-(IC6A-A)") (class "Default")
      (node (ref "IC6") (pin "2") (pinfunction "A_2") (pintype "input"))
      (node (ref "U$1") (pin "P$10") (pinfunction "A14_P$10") (pintype "bidirectional"))
    )
    (net (code "99") (name "Net-(IC6A-B)") (class "Default")
      (node (ref "IC6") (pin "3") (pinfunction "B_3") (pintype "input"))
      (node (ref "U$1") (pin "P$7") (pinfunction "A15_P$7") (pintype "bidirectional"))
    )
    (net (code "100") (name "Net-(IC6A-G)") (class "Default")
      (node (ref "IC6") (pin "1") (pinfunction "G_1") (pintype "input"))
      (node (ref "U$1") (pin "P$1") (pinfunction "RAS*_P$1") (pintype "bidirectional"))
    )
    (net (code "101") (name "Net-(IC6B-B)") (class "Default")
      (node (ref "IC6") (pin "13") (pinfunction "B_13") (pintype "input"))
      (node (ref "U$1") (pin "P$9") (pinfunction "A11_P$9") (pintype "bidirectional"))
    )
    (net (code "102") (name "Net-(IC7A-2C)") (class "Default")
      (node (ref "IC7") (pin "15") (pinfunction "2C_15") (pintype "input"))
      (node (ref "U$1") (pin "P$13") (pinfunction "WR*_P$13") (pintype "bidirectional"))
    )
    (net (code "103") (name "Net-(IC7A-A)") (class "Default")
      (node (ref "IC7") (pin "13") (pinfunction "A_13") (pintype "input"))
      (node (ref "U$1") (pin "P$40") (pinfunction "A2_P$40") (pintype "bidirectional"))
    )
    (net (code "104") (name "Net-(IC7A-B)") (class "Default")
      (node (ref "IC7") (pin "3") (pinfunction "B_3") (pintype "input"))
      (node (ref "U$1") (pin "P$34") (pinfunction "A3_P$34") (pintype "bidirectional"))
    )
    (net (code "105") (name "Net-(IC9-VI)") (class "Default")
      (node (ref "C9") (pin "+") (pinfunction "+_+") (pintype "passive"))
      (node (ref "IC9") (pin "1") (pinfunction "VI_1") (pintype "input"))
      (node (ref "S1") (pin "3") (pinfunction "S_3") (pintype "passive"))
    )
    (net (code "106") (name "Net-(R1-Pad1)") (class "Default")
      (node (ref "R1") (pin "1") (pinfunction "1_1") (pintype "passive"))
      (node (ref "U$2") (pin "7") (pinfunction "7_7") (pintype "bidirectional"))
    )
    (net (code "107") (name "Net-(R2-Pad1)") (class "Default")
      (node (ref "R2") (pin "1") (pinfunction "1_1") (pintype "passive"))
      (node (ref "U$2") (pin "6") (pinfunction "6_6") (pintype "bidirectional"))
    )
    (net (code "108") (name "Net-(R3-Pad1)") (class "Default")
      (node (ref "R3") (pin "1") (pinfunction "1_1") (pintype "passive"))
      (node (ref "U$2") (pin "5") (pinfunction "5_5") (pintype "bidirectional"))
    )
    (net (code "109") (name "Net-(R4-Pad1)") (class "Default")
      (node (ref "R4") (pin "1") (pinfunction "1_1") (pintype "passive"))
      (node (ref "U$2") (pin "4/CANRX") (pinfunction "4/CANRX_4/CANRX") (pintype "bidirectional"))
    )
    (net (code "110") (name "Net-(R5-Pad1)") (class "Default")
      (node (ref "R5") (pin "1") (pinfunction "1_1") (pintype "passive"))
      (node (ref "U$2") (pin "3/CANTX") (pinfunction "3/CANTX_3/CANTX") (pintype "bidirectional"))
    )
    (net (code "111") (name "Net-(R6-Pad1)") (class "Default")
      (node (ref "R6") (pin "1") (pinfunction "1_1") (pintype "passive"))
      (node (ref "U$2") (pin "2") (pinfunction "2_2") (pintype "bidirectional"))
    )
    (net (code "112") (name "Net-(RGB_LED1-BLUE)") (class "Default")
      (node (ref "R1") (pin "2") (pinfunction "2_2") (pintype "passive"))
      (node (ref "RGB_LED1") (pin "1") (pinfunction "BLUE_1") (pintype "bidirectional"))
    )
    (net (code "113") (name "Net-(RGB_LED1-GREEN)") (class "Default")
      (node (ref "R2") (pin "2") (pinfunction "2_2") (pintype "passive"))
      (node (ref "RGB_LED1") (pin "2") (pinfunction "GREEN_2") (pintype "bidirectional"))
    )
    (net (code "114") (name "Net-(RGB_LED1-RED)") (class "Default")
      (node (ref "R3") (pin "2") (pinfunction "2_2") (pintype "passive"))
      (node (ref "RGB_LED1") (pin "4") (pinfunction "RED_4") (pintype "bidirectional"))
    )
    (net (code "115") (name "Net-(RGB_LED2-BLUE)") (class "Default")
      (node (ref "R4") (pin "2") (pinfunction "2_2") (pintype "passive"))
      (node (ref "RGB_LED2") (pin "1") (pinfunction "BLUE_1") (pintype "bidirectional"))
    )
    (net (code "116") (name "Net-(RGB_LED2-GREEN)") (class "Default")
      (node (ref "R5") (pin "2") (pinfunction "2_2") (pintype "passive"))
      (node (ref "RGB_LED2") (pin "2") (pinfunction "GREEN_2") (pintype "bidirectional"))
    )
    (net (code "117") (name "Net-(RGB_LED2-RED)") (class "Default")
      (node (ref "R6") (pin "2") (pinfunction "2_2") (pintype "passive"))
      (node (ref "RGB_LED2") (pin "4") (pinfunction "RED_4") (pintype "bidirectional"))
    )
    (net (code "118") (name "Net-(S1-P)") (class "Default")
      (node (ref "J1") (pin "3") (pinfunction "3_3") (pintype "passive"))
      (node (ref "S1") (pin "2") (pinfunction "P_2") (pintype "passive"))
    )
    (net (code "119") (name "Net-(U$2-Pad3V3_LO)") (class "Default")
      (node (ref "U$2") (pin "3V3_LO") (pinfunction "3V3_LO_3V3_LO") (pintype "bidirectional"))
      (node (ref "U$2") (pin "AREF") (pinfunction "AREF_AREF") (pintype "bidirectional"))
    )
    (net (code "120") (name "VCC") (class "Default")
      (node (ref "B1") (pin "HV") (pinfunction "HV_HV") (pintype "power_in"))
      (node (ref "B2") (pin "HV") (pinfunction "HV_HV") (pintype "power_in"))
      (node (ref "B3") (pin "HV") (pinfunction "HV_HV") (pintype "power_in"))
      (node (ref "B4") (pin "HV") (pinfunction "HV_HV") (pintype "power_in"))
      (node (ref "B5") (pin "HV") (pinfunction "HV_HV") (pintype "power_in"))
      (node (ref "B6") (pin "HV") (pinfunction "HV_HV") (pintype "power_in"))
      (node (ref "C1") (pin "2") (pinfunction "2_2") (pintype "passive"))
      (node (ref "C10") (pin "+") (pinfunction "+_+") (pintype "passive"))
      (node (ref "C11") (pin "1") (pinfunction "1_1") (pintype "passive"))
      (node (ref "C2") (pin "2") (pinfunction "2_2") (pintype "passive"))
      (node (ref "C3") (pin "2") (pinfunction "2_2") (pintype "passive"))
      (node (ref "C4") (pin "2") (pinfunction "2_2") (pintype "passive"))
      (node (ref "C5") (pin "2") (pinfunction "2_2") (pintype "passive"))
      (node (ref "C6") (pin "2") (pinfunction "2_2") (pintype "passive"))
      (node (ref "C7") (pin "2") (pinfunction "2_2") (pintype "passive"))
      (node (ref "C8") (pin "2") (pinfunction "2_2") (pintype "passive"))
      (node (ref "IC1") (pin "14") (pinfunction "VCC_14") (pintype "power_in"))
      (node (ref "IC11") (pin "14") (pinfunction "VCC_14") (pintype "power_in"))
      (node (ref "IC2") (pin "20") (pinfunction "VCC_20") (pintype "power_in"))
      (node (ref "IC3") (pin "14") (pinfunction "VCC_14") (pintype "power_in"))
      (node (ref "IC4") (pin "20") (pinfunction "VCC_20") (pintype "power_in"))
      (node (ref "IC5") (pin "12") (pinfunction "D_12") (pintype "input"))
      (node (ref "IC5") (pin "14") (pinfunction "VCC_14") (pintype "power_in"))
      (node (ref "IC5") (pin "2") (pinfunction "D_2") (pintype "input"))
      (node (ref "IC6") (pin "16") (pinfunction "VCC_16") (pintype "power_in"))
      (node (ref "IC7") (pin "16") (pinfunction "VCC_16") (pintype "power_in"))
      (node (ref "IC9") (pin "3") (pinfunction "VO_3") (pintype "passive"))
      (node (ref "J2") (pin "2") (pinfunction "2_2") (pintype "passive"))
      (node (ref "J3") (pin "2") (pinfunction "2_2") (pintype "passive"))
      (node (ref "R7") (pin "1") (pinfunction "1_1") (pintype "passive"))
      (node (ref "U$2") (pin "VIN") (pinfunction "VIN_VIN") (pintype "bidirectional"))
    )
    (net (code "121") (name "VCC{slash}2") (class "Default")
      (node (ref "B1") (pin "LV") (pinfunction "LV_LV") (pintype "power_in"))
      (node (ref "B2") (pin "LV") (pinfunction "LV_LV") (pintype "power_in"))
      (node (ref "B3") (pin "LV") (pinfunction "LV_LV") (pintype "power_in"))
      (node (ref "B4") (pin "LV") (pinfunction "LV_LV") (pintype "power_in"))
      (node (ref "B5") (pin "LV") (pinfunction "LV_LV") (pintype "power_in"))
      (node (ref "B6") (pin "LV") (pinfunction "LV_LV") (pintype "power_in"))
      (node (ref "U$2") (pin "3V3_2") (pinfunction "3V3_2_3V3_2") (pintype "bidirectional"))
    )
    (net (code "122") (name "unconnected-(IC1C-O-Pad8)") (class "Default")
      (node (ref "IC1") (pin "8") (pinfunction "O_8") (pintype "output"))
    )
    (net (code "123") (name "unconnected-(IC5A-Q-Pad5)") (class "Default")
      (node (ref "IC5") (pin "5") (pinfunction "Q_5") (pintype "output"))
    )
    (net (code "124") (name "unconnected-(IC5B-Q-Pad9)") (class "Default")
      (node (ref "IC5") (pin "9") (pinfunction "Q_9") (pintype "output"))
    )
    (net (code "125") (name "unconnected-(IC6A-Y1-Pad5)") (class "Default")
      (node (ref "IC6") (pin "5") (pinfunction "Y1_5") (pintype "output"))
    )
    (net (code "126") (name "unconnected-(IC6A-Y2-Pad6)") (class "Default")
      (node (ref "IC6") (pin "6") (pinfunction "Y2_6") (pintype "output"))
    )
    (net (code "127") (name "unconnected-(IC6A-Y3-Pad7)") (class "Default")
      (node (ref "IC6") (pin "7") (pinfunction "Y3_7") (pintype "output"))
    )
    (net (code "128") (name "unconnected-(IC6B-Y1-Pad11)") (class "Default")
      (node (ref "IC6") (pin "11") (pinfunction "Y1_11") (pintype "output"))
    )
    (net (code "129") (name "unconnected-(IC6B-Y2-Pad10)") (class "Default")
      (node (ref "IC6") (pin "10") (pinfunction "Y2_10") (pintype "output"))
    )
    (net (code "130") (name "unconnected-(IC6B-Y3-Pad9)") (class "Default")
      (node (ref "IC6") (pin "9") (pinfunction "Y3_9") (pintype "output"))
    )
    (net (code "131") (name "unconnected-(J3-Pad4)") (class "Default")
      (node (ref "J3") (pin "4") (pinfunction "4_4") (pintype "passive"))
    )
    (net (code "132") (name "unconnected-(J3-Pad6)") (class "Default")
      (node (ref "J3") (pin "6") (pinfunction "6_6") (pintype "passive"))
    )
    (net (code "133") (name "unconnected-(J3-Pad8)") (class "Default")
      (node (ref "J3") (pin "8") (pinfunction "8_8") (pintype "passive"))
    )
    (net (code "134") (name "unconnected-(S1-O-Pad1)") (class "Default")
      (node (ref "S1") (pin "1") (pinfunction "O_1") (pintype "passive"))
    )
    (net (code "135") (name "unconnected-(U$1-A4-PadP$31)") (class "Default")
      (node (ref "U$1") (pin "P$31") (pinfunction "A4_P$31") (pintype "bidirectional"))
    )
    (net (code "136") (name "unconnected-(U$1-CAS*-PadP$3)") (class "Default")
      (node (ref "U$1") (pin "P$3") (pinfunction "CAS*_P$3") (pintype "bidirectional"))
    )
    (net (code "137") (name "unconnected-(U$1-IN*-PadP$19)") (class "Default")
      (node (ref "U$1") (pin "P$19") (pinfunction "IN*_P$19") (pintype "bidirectional"))
    )
    (net (code "138") (name "unconnected-(U$1-INTAK*-PadP$14)") (class "Default")
      (node (ref "U$1") (pin "P$14") (pinfunction "INTAK*_P$14") (pintype "bidirectional"))
    )
    (net (code "139") (name "unconnected-(U$1-MUX-PadP$16)") (class "Default")
      (node (ref "U$1") (pin "P$16") (pinfunction "MUX_P$16") (pintype "bidirectional"))
    )
    (net (code "140") (name "unconnected-(U$1-NC-PadP$39)") (class "Default")
      (node (ref "U$1") (pin "P$39") (pinfunction "NC_P$39") (pintype "bidirectional"))
    )
    (net (code "141") (name "unconnected-(U$1-OUT*-PadP$12)") (class "Default")
      (node (ref "U$1") (pin "P$12") (pinfunction "OUT*_P$12") (pintype "bidirectional"))
    )
    (net (code "142") (name "unconnected-(U$1-SYSRES*-PadP$2)") (class "Default")
      (node (ref "U$1") (pin "P$2") (pinfunction "SYSRES*_P$2") (pintype "bidirectional"))
    )
    (net (code "143") (name "unconnected-(U$1-TEST*-PadP$23)") (class "Default")
      (node (ref "U$1") (pin "P$23") (pinfunction "TEST*_P$23") (pintype "bidirectional"))
    )
    (net (code "144") (name "unconnected-(U$2-A21{slash}DAC0-Pad21{slash}DAC0)") (class "Default")
      (node (ref "U$2") (pin "21/DAC0") (pinfunction "A21/DAC0_21/DAC0") (pintype "bidirectional"))
    )
    (net (code "145") (name "unconnected-(U$2-Pad0{slash}RX)") (class "Default")
      (node (ref "U$2") (pin "0/RX") (pinfunction "0/RX_0/RX") (pintype "bidirectional"))
    )
    (net (code "146") (name "unconnected-(U$2-Pad1{slash}TX)") (class "Default")
      (node (ref "U$2") (pin "1/TX") (pinfunction "1/TX_1/TX") (pintype "bidirectional"))
    )
    (net (code "147") (name "unconnected-(U$2-Pad3V3)") (class "Default")
      (node (ref "U$2") (pin "3V3") (pinfunction "3V3_3V3") (pintype "bidirectional"))
    )
    (net (code "148") (name "unconnected-(U$2-Pad14{slash}A0)") (class "Default")
      (node (ref "U$2") (pin "14/A0") (pinfunction "14/A0_14/A0") (pintype "bidirectional"))
    )
    (net (code "149") (name "unconnected-(U$2-Pad16{slash}A2)") (class "Default")
      (node (ref "U$2") (pin "16/A2") (pinfunction "16/A2_16/A2") (pintype "bidirectional"))
    )
    (net (code "150") (name "unconnected-(U$2-Pad17{slash}A3)") (class "Default")
      (node (ref "U$2") (pin "17/A3") (pinfunction "17/A3_17/A3") (pintype "bidirectional"))
    )
    (net (code "151") (name "unconnected-(U$2-Pad18{slash}A4{slash}SDA)") (class "Default")
      (node (ref "U$2") (pin "18/A4/SDA") (pinfunction "18/A4/SDA_18/A4/SDA") (pintype "bidirectional"))
    )
    (net (code "152") (name "unconnected-(U$2-Pad19{slash}A5{slash}SCL)") (class "Default")
      (node (ref "U$2") (pin "19/A5/SCL") (pinfunction "19/A5/SCL_19/A5/SCL") (pintype "bidirectional"))
    )
    (net (code "153") (name "unconnected-(U$2-Pad20{slash}A6)") (class "Default")
      (node (ref "U$2") (pin "20/A6") (pinfunction "20/A6_20/A6") (pintype "bidirectional"))
    )
    (net (code "154") (name "unconnected-(U$2-Pad21{slash}A7)") (class "Default")
      (node (ref "U$2") (pin "21/A7") (pinfunction "21/A7_21/A7") (pintype "bidirectional"))
    )
    (net (code "155") (name "unconnected-(U$2-Pad24)") (class "Default")
      (node (ref "U$2") (pin "24") (pinfunction "24_24") (pintype "bidirectional"))
    )
    (net (code "156") (name "unconnected-(U$2-PadA10)") (class "Default")
      (node (ref "U$2") (pin "A10") (pinfunction "A10_A10") (pintype "bidirectional"))
    )
    (net (code "157") (name "unconnected-(U$2-PadA11)") (class "Default")
      (node (ref "U$2") (pin "A11") (pinfunction "A11_A11") (pintype "bidirectional"))
    )
    (net (code "158") (name "unconnected-(U$2-PadA22{slash}DAC1)") (class "Default")
      (node (ref "U$2") (pin "A22/DAC1") (pinfunction "A22/DAC1_A22/DAC1") (pintype "bidirectional"))
    )
    (net (code "159") (name "unconnected-(U$2-PadPROG)") (class "Default")
      (node (ref "U$2") (pin "PROG") (pinfunction "PROG_PROG") (pintype "bidirectional"))
    )
    (net (code "160") (name "unconnected-(U$2-PadRESET)") (class "Default")
      (node (ref "U$2") (pin "RESET") (pinfunction "RESET_RESET") (pintype "bidirectional"))
    )
    (net (code "161") (name "unconnected-(U$2-PadU5V)") (class "Default")
      (node (ref "U$2") (pin "U5V") (pinfunction "U5V_U5V") (pintype "bidirectional"))
    )
    (net (code "162") (name "unconnected-(U$2-PadUD+)") (class "Default")
      (node (ref "U$2") (pin "UD+") (pinfunction "UD+_UD+") (pintype "bidirectional"))
    )
    (net (code "163") (name "unconnected-(U$2-PadUD-)") (class "Default")
      (node (ref "U$2") (pin "UD-") (pinfunction "UD-_UD-") (pintype "bidirectional"))
    )
    (net (code "164") (name "unconnected-(U$2-PadVBAT)") (class "Default")
      (node (ref "U$2") (pin "VBAT") (pinfunction "VBAT_VBAT") (pintype "bidirectional"))
    )
    (net (code "165") (name "unconnected-(U$2-PadVUSB)") (class "Default")
      (node (ref "U$2") (pin "VUSB") (pinfunction "VUSB_VUSB") (pintype "bidirectional"))
    )
  )
)
